# H_BRIDGE.net
KiCad netlist of a schematic drawn in Altium Designer
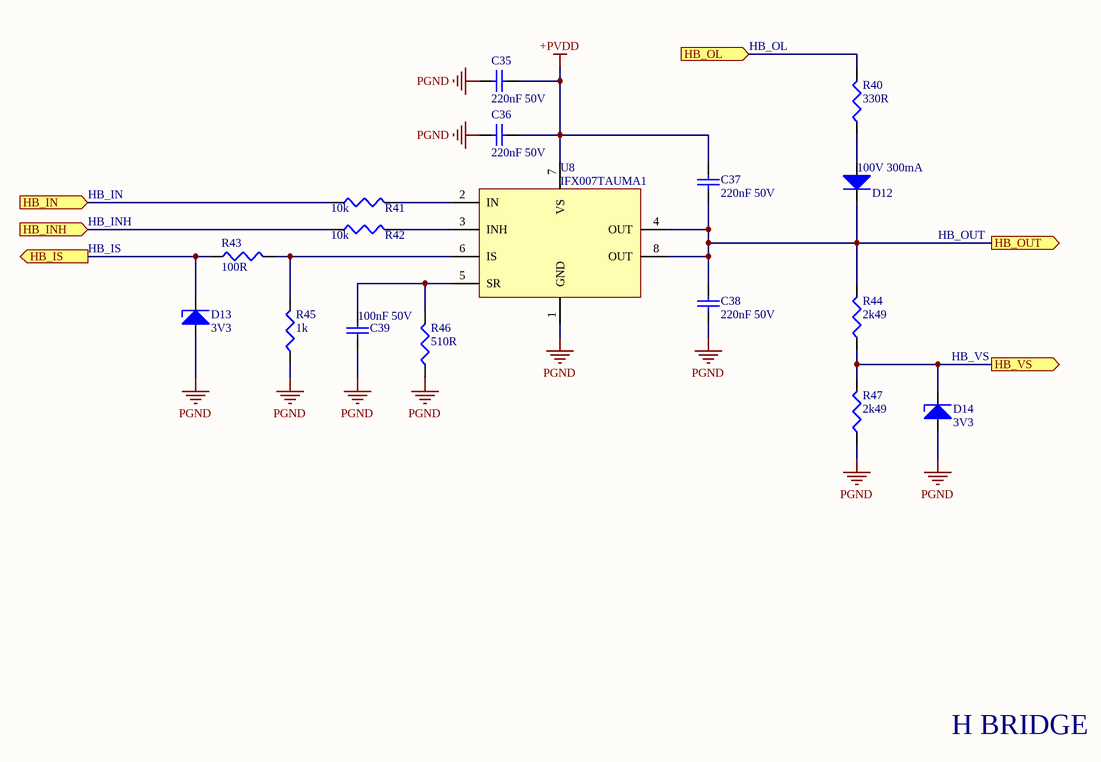
[diagram p0: H_BRIDGE.SchDoc]

(export (version "E")
  (design (tool "Eeschema 10.0.6"))
  (components
    (comp (ref "C35")
      (value "220nF 50V")
      (footprint "CAP1206")
      (description "CAP CER 0.22UF 50V X7R 1206")
      (libsource (lib "SMALL_BCM") (part "CAP1206_220nF"))
    )
    (comp (ref "C36")
      (value "220nF 50V")
      (footprint "CAP1206")
      (description "CAP CER 0.22UF 50V X7R 1206")
      (libsource (lib "SMALL_BCM") (part "CAP1206_220nF"))
    )
    (comp (ref "C37")
      (value "220nF 50V")
      (footprint "CAP1206")
      (description "CAP CER 0.22UF 50V X7R 1206")
      (libsource (lib "SMALL_BCM") (part "CAP1206_220nF"))
    )
    (comp (ref "C38")
      (value "220nF 50V")
      (footprint "CAP1206")
      (description "CAP CER 0.22UF 50V X7R 1206")
      (libsource (lib "SMALL_BCM") (part "CAP1206_220nF"))
    )
    (comp (ref "C39")
      (value "100nF 50V")
      (footprint "CAP0603")
      (description "CAP CER 0.1UF 50V X7R 0603")
      (libsource (lib "SMALL_BCM") (part "CAP0603_100nF"))
    )
    (comp (ref "D12")
      (value "100V 300mA")
      (footprint "SOD123_1N4148W-7-F")
      (description "DIODE GEN PURP 100V 300MA SOD123")
      (libsource (lib "SMALL_BCM") (part "DIODE_1N4148W-7-F"))
    )
    (comp (ref "D13")
      (value "3V3")
      (footprint "SOD323")
      (description "DIODE ZENER 3.3V 300MW SOD323")
      (libsource (lib "SMALL_BCM") (part "ZENER_3V3_MM3Z3V3T1G"))
    )
    (comp (ref "D14")
      (value "3V3")
      (footprint "SOD323")
      (description "DIODE ZENER 3.3V 300MW SOD323")
      (libsource (lib "SMALL_BCM") (part "ZENER_3V3_MM3Z3V3T1G"))
    )
    (comp (ref "R40")
      (value "330R")
      (footprint "RES0603")
      (description "RES 330 OHM 1% 1/10W 0603")
      (libsource (lib "SMALL_BCM") (part "RES0603_330R"))
    )
    (comp (ref "R41")
      (value "10k")
      (footprint "RES0603")
      (description "RES SMD 10K OHM 5% 1/10W 0603")
      (libsource (lib "SMALL_BCM") (part "RES0603_10k"))
    )
    (comp (ref "R42")
      (value "10k")
      (footprint "RES0603")
      (description "RES SMD 10K OHM 5% 1/10W 0603")
      (libsource (lib "SMALL_BCM") (part "RES0603_10k"))
    )
    (comp (ref "R43")
      (value "100R")
      (footprint "RES0603")
      (description "RES SMD 100R OHM 1% 1/10W 0603")
      (libsource (lib "SMALL_BCM") (part "RES0603_100R"))
    )
    (comp (ref "R44")
      (value "2k49")
      (footprint "RES0603")
      (description "RES 2.49K OHM 1% 1/10W 0603")
      (libsource (lib "SMALL_BCM") (part "RES0603_2k49"))
    )
    (comp (ref "R45")
      (value "1k")
      (footprint "RES0603")
      (description "RES SMD 1K OHM 1% 1/10W 0603")
      (libsource (lib "SMALL_BCM") (part "RES0603_1k"))
    )
    (comp (ref "R46")
      (value "510R")
      (footprint "RES0603")
      (description "RES 510R OHM 1% 1/10W 0603")
      (libsource (lib "SMALL_BCM") (part "RES0603_510R"))
    )
    (comp (ref "R47")
      (value "2k49")
      (footprint "RES0603")
      (description "RES 2.49K OHM 1% 1/10W 0603")
      (libsource (lib "SMALL_BCM") (part "RES0603_2k49"))
    )
    (comp (ref "U8")
      (value "55A")
      (footprint "TO-263-8")
      (description "IC HALF-BRIDGE DRVR 2 CH TO263")
      (fields (field (name "P/N") "IFX007TAUMA1"))
      (libsource (lib "SMALL_BCM") (part "HB_IFX007TAUMA1"))
    )
  )
  (nets
    (net (code "1") (name "+PVDD") (class "Default")
      (node (ref "C35") (pin "2") (pinfunction "2_2") (pintype "passive"))
      (node (ref "C36") (pin "2") (pinfunction "2_2") (pintype "passive"))
      (node (ref "C37") (pin "1") (pinfunction "1_1") (pintype "passive"))
      (node (ref "U8") (pin "7") (pinfunction "VS_7") (pintype "power_in"))
    )
    (net (code "2") (name "/HB_IN") (class "Default")
      (node (ref "R41") (pin "1") (pinfunction "1_1") (pintype "passive"))
    )
    (net (code "3") (name "/HB_INH") (class "Default")
      (node (ref "R42") (pin "1") (pinfunction "1_1") (pintype "passive"))
    )
    (net (code "4") (name "/HB_IS") (class "Default")
      (node (ref "D13") (pin "1") (pinfunction "K_1") (pintype "passive"))
      (node (ref "R43") (pin "1") (pinfunction "1_1") (pintype "passive"))
    )
    (net (code "5") (name "/HB_OL") (class "Default")
      (node (ref "R40") (pin "2") (pinfunction "2_2") (pintype "passive"))
    )
    (net (code "6") (name "/HB_OUT") (class "Default")
      (node (ref "C37") (pin "2") (pinfunction "2_2") (pintype "passive"))
      (node (ref "C38") (pin "1") (pinfunction "1_1") (pintype "passive"))
      (node (ref "D12") (pin "2") (pinfunction "K_2") (pintype "passive"))
      (node (ref "R44") (pin "2") (pinfunction "2_2") (pintype "passive"))
      (node (ref "U8") (pin "4") (pinfunction "OUT_4") (pintype "passive"))
      (node (ref "U8") (pin "8") (pinfunction "OUT_8") (pintype "passive"))
    )
    (net (code "7") (name "/HB_VS") (class "Default")
      (node (ref "D14") (pin "1") (pinfunction "K_1") (pintype "passive"))
      (node (ref "R44") (pin "1") (pinfunction "1_1") (pintype "passive"))
      (node (ref "R47") (pin "2") (pinfunction "2_2") (pintype "passive"))
    )
    (net (code "8") (name "Net-(D12-A)") (class "Default")
      (node (ref "D12") (pin "1") (pinfunction "A_1") (pintype "passive"))
      (node (ref "R40") (pin "1") (pinfunction "1_1") (pintype "passive"))
    )
    (net (code "9") (name "Net-(U8-IN)") (class "Default")
      (node (ref "R41") (pin "2") (pinfunction "2_2") (pintype "passive"))
      (node (ref "U8") (pin "2") (pinfunction "IN_2") (pintype "passive"))
    )
    (net (code "10") (name "Net-(U8-INH)") (class "Default")
      (node (ref "R42") (pin "2") (pinfunction "2_2") (pintype "passive"))
      (node (ref "U8") (pin "3") (pinfunction "INH_3") (pintype "passive"))
    )
    (net (code "11") (name "Net-(U8-IS)") (class "Default")
      (node (ref "R43") (pin "2") (pinfunction "2_2") (pintype "passive"))
      (node (ref "R45") (pin "2") (pinfunction "2_2") (pintype "passive"))
      (node (ref "U8") (pin "6") (pinfunction "IS_6") (pintype "passive"))
    )
    (net (code "12") (name "Net-(U8-SR)") (class "Default")
      (node (ref "C39") (pin "2") (pinfunction "2_2") (pintype "passive"))
      (node (ref "R46") (pin "2") (pinfunction "2_2") (pintype "passive"))
      (node (ref "U8") (pin "5") (pinfunction "SR_5") (pintype "passive"))
    )
    (net (code "13") (name "PGND") (class "Default")
      (node (ref "C35") (pin "1") (pinfunction "1_1") (pintype "passive"))
      (node (ref "C36") (pin "1") (pinfunction "1_1") (pintype "passive"))
      (node (ref "C38") (pin "2") (pinfunction "2_2") (pintype "passive"))
      (node (ref "C39") (pin "1") (pinfunction "1_1") (pintype "passive"))
      (node (ref "D13") (pin "2") (pinfunction "A_2") (pintype "passive"))
      (node (ref "D14") (pin "2") (pinfunction "A_2") (pintype "passive"))
      (node (ref "R45") (pin "1") (pinfunction "1_1") (pintype "passive"))
      (node (ref "R46") (pin "1") (pinfunction "1_1") (pintype "passive"))
      (node (ref "R47") (pin "1") (pinfunction "1_1") (pintype "passive"))
      (node (ref "U8") (pin "1") (pinfunction "GND_1") (pintype "power_in"))
    )
  )
)
